# LevelShifter.net
KiCad netlist of a schematic drawn in Altium Designer
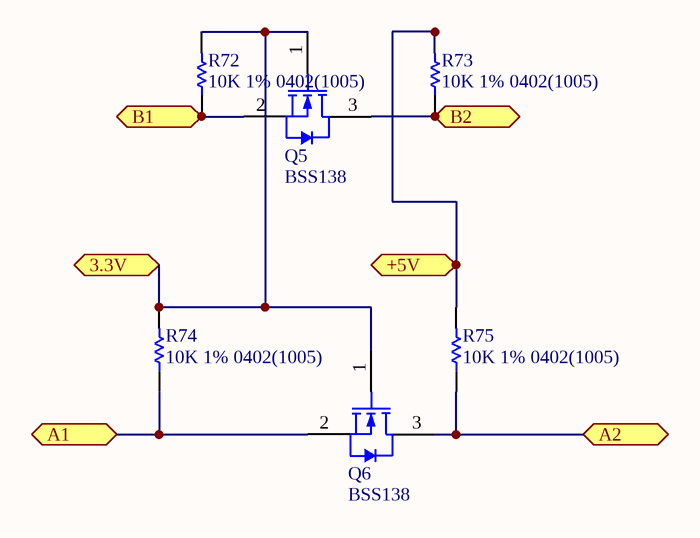
[diagram p0: LevelShifter.SchDoc]

(export (version "E")
  (design (tool "Eeschema 10.0.6"))
  (components
    (comp (ref "Q5")
      (value "BSS138")
      (footprint "FAIR-SOT23-3_V")
      (fields (field (name "TOLERANCE") "30ppm"))
      (libsource (lib "Altium Content Vault") (part "NEMOS-GSD-3"))
    )
    (comp (ref "Q6")
      (value "BSS138")
      (footprint "FAIR-SOT23-3_V")
      (fields (field (name "TOLERANCE") "30ppm"))
      (libsource (lib "Altium Content Vault") (part "NEMOS-GSD-3"))
    )
    (comp (ref "R72")
      (value "10K 1% 0402(1005)")
      (footprint "RESC0402(1005)_L")
      (description "10K 0.063W 1% 0402 (1005 Metric)  SMD")
      (fields (field (name "TOLERANCE") "1 %") (field (name "POWER") "0.063 W"))
      (libsource (lib "Altium Content Vault") (part "RES"))
    )
    (comp (ref "R73")
      (value "10K 1% 0402(1005)")
      (footprint "RESC0402(1005)_L")
      (description "10K 0.063W 1% 0402 (1005 Metric)  SMD")
      (fields (field (name "TOLERANCE") "1 %") (field (name "POWER") "0.063 W"))
      (libsource (lib "Altium Content Vault") (part "RES"))
    )
    (comp (ref "R74")
      (value "10K 1% 0402(1005)")
      (footprint "RESC0402(1005)_L")
      (description "10K 0.063W 1% 0402 (1005 Metric)  SMD")
      (fields (field (name "TOLERANCE") "1 %") (field (name "POWER") "0.063 W"))
      (libsource (lib "Altium Content Vault") (part "RES"))
    )
    (comp (ref "R75")
      (value "10K 1% 0402(1005)")
      (footprint "RESC0402(1005)_L")
      (description "10K 0.063W 1% 0402 (1005 Metric)  SMD")
      (fields (field (name "TOLERANCE") "1 %") (field (name "POWER") "0.063 W"))
      (libsource (lib "Altium Content Vault") (part "RES"))
    )
  )
  (nets
    (net (code "1") (name "/+5V") (class "Default")
      (node (ref "R73") (pin "2") (pinfunction "2_2") (pintype "passive"))
      (node (ref "R75") (pin "2") (pinfunction "2_2") (pintype "passive"))
    )
    (net (code "2") (name "/3.3V") (class "Default")
      (node (ref "Q5") (pin "1") (pinfunction "G_1") (pintype "passive"))
      (node (ref "Q6") (pin "1") (pinfunction "G_1") (pintype "passive"))
      (node (ref "R72") (pin "2") (pinfunction "2_2") (pintype "passive"))
      (node (ref "R74") (pin "2") (pinfunction "2_2") (pintype "passive"))
    )
    (net (code "3") (name "/A1") (class "Default")
      (node (ref "Q6") (pin "2") (pinfunction "S_2") (pintype "passive"))
      (node (ref "R74") (pin "1") (pinfunction "1_1") (pintype "passive"))
    )
    (net (code "4") (name "/A2") (class "Default")
      (node (ref "Q6") (pin "3") (pinfunction "D_3") (pintype "passive"))
      (node (ref "R75") (pin "1") (pinfunction "1_1") (pintype "passive"))
    )
    (net (code "5") (name "/B1") (class "Default")
      (node (ref "Q5") (pin "2") (pinfunction "S_2") (pintype "passive"))
      (node (ref "R72") (pin "1") (pinfunction "1_1") (pintype "passive"))
    )
    (net (code "6") (name "/B2") (class "Default")
      (node (ref "Q5") (pin "3") (pinfunction "D_3") (pintype "passive"))
      (node (ref "R73") (pin "1") (pinfunction "1_1") (pintype "passive"))
    )
  )
)
